# P02_XDS100v2.net
KiCad netlist of a schematic drawn in Altium Designer
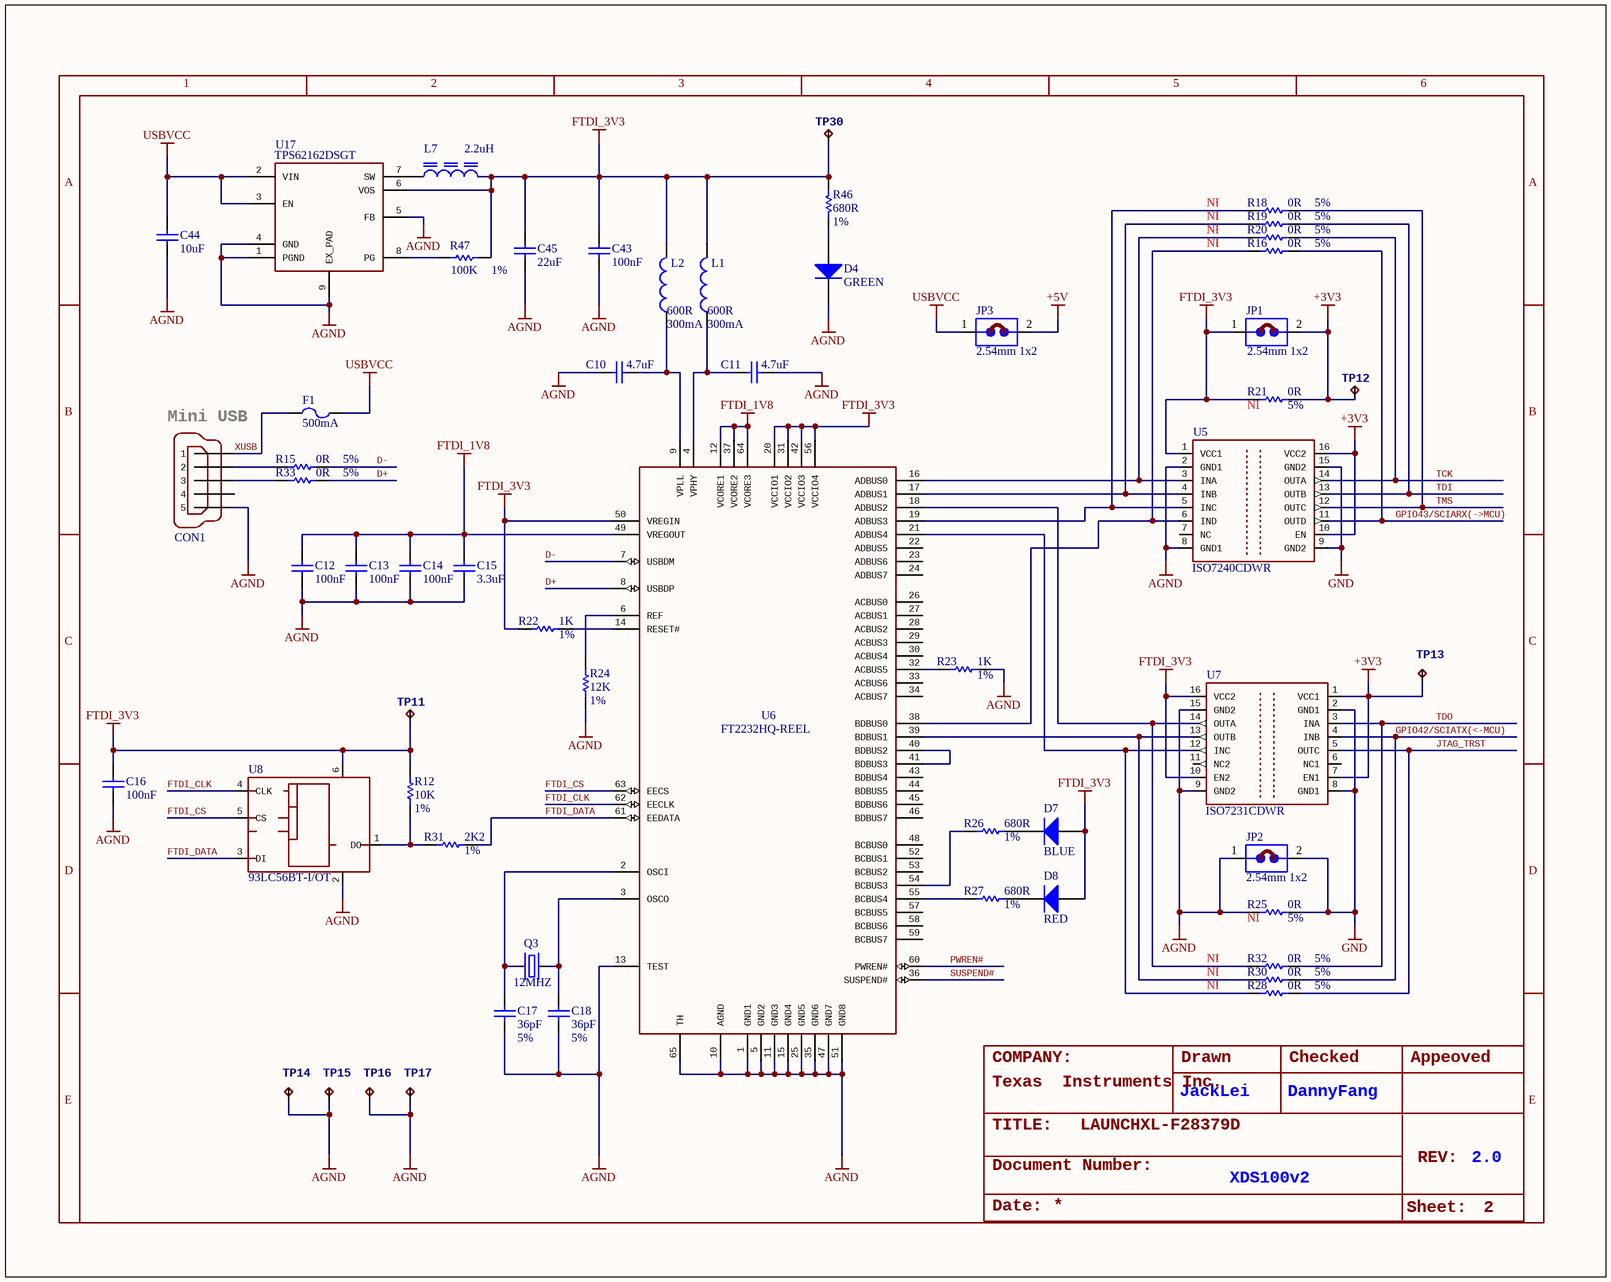
[diagram p0: P02_XDS100v2.SchDoc]

(export (version "E")
  (design (tool "Eeschema 10.0.6"))
  (components
    (comp (ref "C10")
      (value "4.7uF")
      (footprint "C0402")
      (description "CAP,4.7UF,+/-20%,X5R,6.3V,SMD0402 fix PN add D（20151023）")
      (fields
        (field (name "MANUFACTURER") "MURATA")
        (field (name "MANUFACTURER PART NUMBER") "GRM155R60J475ME47D")
      )
      (libsource (lib "Embest") (part "C"))
    )
    (comp (ref "C11")
      (value "4.7uF")
      (footprint "C0402")
      (description "CAP,4.7UF,+/-20%,X5R,6.3V,SMD0402 fix PN add D（20151023）")
      (fields
        (field (name "MANUFACTURER") "MURATA")
        (field (name "MANUFACTURER PART NUMBER") "GRM155R60J475ME47D")
      )
      (libsource (lib "Embest") (part "C"))
    )
    (comp (ref "C12")
      (value "100nF")
      (footprint "C0402")
      (description "CAP,100NF(0.1uf),+/-10%,X5R,10V,SMD0402")
      (fields
        (field (name "MANUFACTURER") "MURATA")
        (field (name "MANUFACTURER PART NUMBER") "GRM155R61A104KA01D")
      )
      (libsource (lib "Embest") (part "C"))
    )
    (comp (ref "C13")
      (value "100nF")
      (footprint "C0402")
      (description "CAP,100NF(0.1uf),+/-10%,X5R,10V,SMD0402")
      (fields
        (field (name "MANUFACTURER") "MURATA")
        (field (name "MANUFACTURER PART NUMBER") "GRM155R61A104KA01D")
      )
      (libsource (lib "Embest") (part "C"))
    )
    (comp (ref "C14")
      (value "100nF")
      (footprint "C0402")
      (description "CAP,100NF(0.1uf),+/-10%,X5R,10V,SMD0402")
      (fields
        (field (name "MANUFACTURER") "MURATA")
        (field (name "MANUFACTURER PART NUMBER") "GRM155R61A104KA01D")
      )
      (libsource (lib "Embest") (part "C"))
    )
    (comp (ref "C15")
      (value "3.3uF")
      (footprint "C0603")
      (description "CAP,3.3uF,+/-10%,X5R,10V,SMD0603")
      (fields
        (field (name "MANUFACTURER") "MURATA")
        (field (name "MANUFACTURER PART NUMBER") "GRM188R61A335KE15D")
      )
      (libsource (lib "Embest") (part "C"))
    )
    (comp (ref "C16")
      (value "100nF")
      (footprint "C0402")
      (description "CAP,100NF(0.1uf),+/-10%,X5R,10V,SMD0402")
      (fields
        (field (name "MANUFACTURER") "MURATA")
        (field (name "MANUFACTURER PART NUMBER") "GRM155R61A104KA01D")
      )
      (libsource (lib "Embest") (part "C"))
    )
    (comp (ref "C17")
      (value "36pF")
      (footprint "C0402")
      (description "CAP,36pF,+/-5%,C0G,50V,SMD0402")
      (fields
        (field (name "RATING") "5%")
        (field (name "MANUFACTURER") "MURATA")
        (field (name "MANUFACTURER PART NUMBER") "GRM1555C1H360JA01D")
      )
      (libsource (lib "Embest") (part "C"))
    )
    (comp (ref "C18")
      (value "36pF")
      (footprint "C0402")
      (description "CAP,36pF,+/-5%,C0G,50V,SMD0402")
      (fields
        (field (name "RATING") "5%")
        (field (name "MANUFACTURER") "MURATA")
        (field (name "MANUFACTURER PART NUMBER") "GRM1555C1H360JA01D")
      )
      (libsource (lib "Embest") (part "C"))
    )
    (comp (ref "C43")
      (value "100nF")
      (footprint "C0402")
      (description "CAP,100NF(0.1uf),+/-10%,X5R,10V,SMD0402")
      (fields
        (field (name "MANUFACTURER") "MURATA")
        (field (name "MANUFACTURER PART NUMBER") "GRM155R61A104KA01D")
      )
      (libsource (lib "Embest") (part "C"))
    )
    (comp (ref "C44")
      (value "10uF")
      (footprint "C1210")
      (description "CAP,10UF,+/-10%,X7R,25V,SMD1210")
      (fields
        (field (name "MANUFACTURER") "MURATA")
        (field (name "MANUFACTURER PART NUMBER") "GRM32DR71E106KA12L")
      )
      (libsource (lib "Embest") (part "C"))
    )
    (comp (ref "C45")
      (value "22uF")
      (footprint "C1210")
      (description "CAP,22UF,+/-10%,X7R,25V,SMD1210")
      (fields
        (field (name "MANUFACTURER") "MURATA")
        (field (name "MANUFACTURER PART NUMBER") "GRM32ER61E226KE15L")
      )
      (libsource (lib "Embest") (part "C"))
    )
    (comp (ref "CON1")
      (value "897-43-005-00-100001")
      (footprint "USB-MINI-B-5P-SMD")
      (description "Connector,MiniUSB B port,5 position,Right Angle,Gold flash 30u,black,SMD")
      (fields (field (name "MANUFACTURER") "MILL-MAX"))
      (libsource (lib "Embest") (part "MINI-USB-32005-201"))
    )
    (comp (ref "D4")
      (value "GREEN")
      (footprint "D0805")
      (description "LED, Bright GREEN , 570nm,30mA,SMD,0805")
      (fields (field (name "MANUFACTURER") "WURTH") (field (name "MANUFACTURER PART NUMBER") "150080VS75000"))
      (libsource (lib "Embest") (part "D"))
    )
    (comp (ref "D7")
      (value "BLUE")
      (footprint "D0805")
      (description "LED, BLUE ,470NM, 30mA,SMD,0805")
      (fields (field (name "MANUFACTURER") "WURTH") (field (name "MANUFACTURER PART NUMBER") "150080BS75000"))
      (libsource (lib "Embest") (part "D"))
    )
    (comp (ref "D8")
      (value "RED")
      (footprint "D0805")
      (description "LED, SUPPER RED ,630NM,30mA, SMD,0805")
      (fields (field (name "MANUFACTURER") "WURTH") (field (name "MANUFACTURER PART NUMBER") "150080SS75000"))
      (libsource (lib "Embest") (part "D"))
    )
    (comp (ref "F1")
      (value "500mA")
      (footprint "FUSM4632X85N")
      (description "PTC RESETTABLE .50A 15V 1812")
      (fields (field (name "MANUFACTURER") "BOURNS") (field (name "MANUFACTURER PART NUMBER") "MF-MSMF050-2"))
      (libsource (lib "Embest") (part "F"))
    )
    (comp (ref "JP1")
      (value "2.54mm 1x2")
      (footprint "HDRV2W64P254_1X2_508X250X850P")
      (fields
        (field (name "MANUFACTURER") "CHIN-BAN")
        (field (name "MANUFACTURER PART NUMBER") "P6E02A-602530-B1")
      )
      (libsource (lib "Embest") (part "SIP2"))
    )
    (comp (ref "JP2")
      (value "2.54mm 1x2")
      (footprint "HDRV2W64P254_1X2_508X250X850P")
      (fields
        (field (name "MANUFACTURER") "CHIN-BAN")
        (field (name "MANUFACTURER PART NUMBER") "P6E02A-602530-B1")
      )
      (libsource (lib "Embest") (part "SIP2"))
    )
    (comp (ref "JP3")
      (value "2.54mm 1x2")
      (footprint "HDRV2W64P254_1X2_508X250X850P")
      (fields
        (field (name "MANUFACTURER") "CHIN-BAN")
        (field (name "MANUFACTURER PART NUMBER") "P6E02A-602530-B1")
      )
      (libsource (lib "Embest") (part "SIP2"))
    )
    (comp (ref "L1")
      (value "600R")
      (footprint "L0402")
      (description "Ferrite Bead,600ohm@100MHz,+/-25%,300mA,0.6ohm,SMD0402")
      (fields
        (field (name "RATING") "300mA")
        (field (name "MANUFACTURER") "MURATA")
        (field (name "MANUFACTURER PART NUMBER") "BLM15AG601SN1D")
      )
      (libsource (lib "Embest") (part "FB"))
    )
    (comp (ref "L2")
      (value "600R")
      (footprint "L0402")
      (description "Ferrite Bead,600ohm@100MHz,+/-25%,300mA,0.6ohm,SMD0402")
      (fields
        (field (name "RATING") "300mA")
        (field (name "MANUFACTURER") "MURATA")
        (field (name "MANUFACTURER PART NUMBER") "BLM15AG601SN1D")
      )
      (libsource (lib "Embest") (part "FB"))
    )
    (comp (ref "L7")
      (value "2.2uH")
      (footprint "INDC300X300X180N")
      (description "Power Inductor,Magnetic shielded,2.2uH,1.6A,0.06ohm,3.0X3.0X1.8mm,SMD")
      (fields
        (field (name "MANUFACTURER") "SUMIDA")
        (field (name "MANUFACTURER PART NUMBER") "CDRH2D18/HPNP-2R2NC")
      )
      (libsource (lib "Embest") (part "L"))
    )
    (comp (ref "Q3")
      (value "12MHZ")
      (footprint "XTAL1140X470X330N")
      (description "Crystal 12MHz ±30ppm (Tol) ±30ppm (Stability) 18pF FUND 50Ohm 2-Pin HC-49/US SMD T/R")
      (fields
        (field (name "MANUFACTURER") "ABRACON")
        (field (name "MANUFACTURER PART NUMBER") "ABLS2-12.000MHZ-D4Y-T")
      )
      (libsource (lib "Embest") (part "X"))
    )
    (comp (ref "R12")
      (value "10K")
      (footprint "R0402")
      (description "RES,10K,+/-1%,1/16W,SMD0402")
      (fields
        (field (name "RATING") "1%")
        (field (name "MANUFACTURER") "YAGEO")
        (field (name "MANUFACTURER PART NUMBER") "RC0402FR-0710KL")
      )
      (libsource (lib "Embest") (part "R"))
    )
    (comp (ref "R15")
      (value "0R")
      (footprint "R0402")
      (description "RES,0R,+/-5%,1/16W,SMD0402")
      (fields
        (field (name "RATING") "5%")
        (field (name "MANUFACTURER") "YAGEO")
        (field (name "MANUFACTURER PART NUMBER") "RC0402JR-070RL")
      )
      (libsource (lib "Embest") (part "R"))
    )
    (comp (ref "R16")
      (value "0R")
      (footprint "R1206")
      (description "RES,0R,+/-5%,1/2W,SMD1206")
      (fields
        (field (name "RATING") "5%")
        (field (name "ASSY") "NI")
        (field (name "MANUFACTURER") "YAGEO")
        (field (name "MANUFACTURER PART NUMBER") "RC1206JR-7W0RL")
      )
      (libsource (lib "Embest") (part "R"))
    )
    (comp (ref "R18")
      (value "0R")
      (footprint "R1206")
      (description "RES,0R,+/-5%,1/2W,SMD1206")
      (fields
        (field (name "RATING") "5%")
        (field (name "ASSY") "NI")
        (field (name "MANUFACTURER") "YAGEO")
        (field (name "MANUFACTURER PART NUMBER") "RC1206JR-7W0RL")
      )
      (libsource (lib "Embest") (part "R"))
    )
    (comp (ref "R19")
      (value "0R")
      (footprint "R1206")
      (description "RES,0R,+/-5%,1/2W,SMD1206")
      (fields
        (field (name "RATING") "5%")
        (field (name "ASSY") "NI")
        (field (name "MANUFACTURER") "YAGEO")
        (field (name "MANUFACTURER PART NUMBER") "RC1206JR-7W0RL")
      )
      (libsource (lib "Embest") (part "R"))
    )
    (comp (ref "R20")
      (value "0R")
      (footprint "R1206")
      (description "RES,0R,+/-5%,1/2W,SMD1206")
      (fields
        (field (name "RATING") "5%")
        (field (name "ASSY") "NI")
        (field (name "MANUFACTURER") "YAGEO")
        (field (name "MANUFACTURER PART NUMBER") "RC1206JR-7W0RL")
      )
      (libsource (lib "Embest") (part "R"))
    )
    (comp (ref "R21")
      (value "0R")
      (footprint "R1206")
      (description "RES,0R,+/-5%,1/2W,SMD1206")
      (fields
        (field (name "RATING") "5%")
        (field (name "ASSY") "NI")
        (field (name "MANUFACTURER") "YAGEO")
        (field (name "MANUFACTURER PART NUMBER") "RC1206JR-7W0RL")
      )
      (libsource (lib "Embest") (part "R"))
    )
    (comp (ref "R22")
      (value "1K")
      (footprint "R0402")
      (description "RES,1K,+/-1%,1/16W,SMD0402")
      (fields
        (field (name "RATING") "1%")
        (field (name "MANUFACTURER") "YAGEO")
        (field (name "MANUFACTURER PART NUMBER") "RC0402FR-071KL")
      )
      (libsource (lib "Embest") (part "R"))
    )
    (comp (ref "R23")
      (value "1K")
      (footprint "R0402")
      (description "RES,1K,+/-1%,1/16W,SMD0402")
      (fields
        (field (name "RATING") "1%")
        (field (name "MANUFACTURER") "YAGEO")
        (field (name "MANUFACTURER PART NUMBER") "RC0402FR-071KL")
      )
      (libsource (lib "Embest") (part "R"))
    )
    (comp (ref "R24")
      (value "12K")
      (footprint "R0402")
      (description "RES,12K,+/-1%,1/16W,SMD0402")
      (fields
        (field (name "RATING") "1%")
        (field (name "MANUFACTURER") "YAGEO")
        (field (name "MANUFACTURER PART NUMBER") "RC0402FR-0712KL")
      )
      (libsource (lib "Embest") (part "R"))
    )
    (comp (ref "R25")
      (value "0R")
      (footprint "R1206")
      (description "RES,0R,+/-5%,1/2W,SMD1206")
      (fields
        (field (name "RATING") "5%")
        (field (name "ASSY") "NI")
        (field (name "MANUFACTURER") "YAGEO")
        (field (name "MANUFACTURER PART NUMBER") "RC1206JR-7W0RL")
      )
      (libsource (lib "Embest") (part "R"))
    )
    (comp (ref "R26")
      (value "680R")
      (footprint "R0402")
      (description "RES,680R,+/-1%,1/16W,SMD0402")
      (fields
        (field (name "RATING") "1%")
        (field (name "MANUFACTURER") "YAGEO")
        (field (name "MANUFACTURER PART NUMBER") "RC0402FR-07680RL")
      )
      (libsource (lib "Embest") (part "R"))
    )
    (comp (ref "R27")
      (value "680R")
      (footprint "R0402")
      (description "RES,680R,+/-1%,1/16W,SMD0402")
      (fields
        (field (name "RATING") "1%")
        (field (name "MANUFACTURER") "YAGEO")
        (field (name "MANUFACTURER PART NUMBER") "RC0402FR-07680RL")
      )
      (libsource (lib "Embest") (part "R"))
    )
    (comp (ref "R28")
      (value "0R")
      (footprint "R1206")
      (description "RES,0R,+/-5%,1/2W,SMD1206")
      (fields
        (field (name "RATING") "5%")
        (field (name "ASSY") "NI")
        (field (name "MANUFACTURER") "YAGEO")
        (field (name "MANUFACTURER PART NUMBER") "RC1206JR-7W0RL")
      )
      (libsource (lib "Embest") (part "R"))
    )
    (comp (ref "R30")
      (value "0R")
      (footprint "R1206")
      (description "RES,0R,+/-5%,1/2W,SMD1206")
      (fields
        (field (name "RATING") "5%")
        (field (name "ASSY") "NI")
        (field (name "MANUFACTURER") "YAGEO")
        (field (name "MANUFACTURER PART NUMBER") "RC1206JR-7W0RL")
      )
      (libsource (lib "Embest") (part "R"))
    )
    (comp (ref "R31")
      (value "2K2")
      (footprint "R0402")
      (description "RES,2K2,+/-1%,1/16W,SMD0402")
      (fields
        (field (name "RATING") "1%")
        (field (name "MANUFACTURER") "YAGEO")
        (field (name "MANUFACTURER PART NUMBER") "RC0402FR-072K2L")
      )
      (libsource (lib "Embest") (part "R"))
    )
    (comp (ref "R32")
      (value "0R")
      (footprint "R1206")
      (description "RES,0R,+/-5%,1/2W,SMD1206")
      (fields
        (field (name "RATING") "5%")
        (field (name "ASSY") "NI")
        (field (name "MANUFACTURER") "YAGEO")
        (field (name "MANUFACTURER PART NUMBER") "RC1206JR-7W0RL")
      )
      (libsource (lib "Embest") (part "R"))
    )
    (comp (ref "R33")
      (value "0R")
      (footprint "R0402")
      (description "RES,0R,+/-5%,1/16W,SMD0402")
      (fields
        (field (name "RATING") "5%")
        (field (name "MANUFACTURER") "YAGEO")
        (field (name "MANUFACTURER PART NUMBER") "RC0402JR-070RL")
      )
      (libsource (lib "Embest") (part "R"))
    )
    (comp (ref "R46")
      (value "680R")
      (footprint "R0402")
      (description "RES,680R,+/-1%,1/16W,SMD0402")
      (fields
        (field (name "RATING") "1%")
        (field (name "MANUFACTURER") "YAGEO")
        (field (name "MANUFACTURER PART NUMBER") "RC0402FR-07680RL")
      )
      (libsource (lib "Embest") (part "R"))
    )
    (comp (ref "R47")
      (value "100K")
      (footprint "R0402")
      (description "RES,100K,+/-1%,1/16W,SMD0402")
      (fields
        (field (name "RATING") "1%")
        (field (name "MANUFACTURER") "YAGEO")
        (field (name "MANUFACTURER PART NUMBER") "RC0402FR-07100KL")
      )
      (libsource (lib "Embest") (part "R"))
    )
    (comp (ref "TP11")
      (value "TESTPAD_TPB1,27")
      (footprint "TESTPAD_B1,27")
      (description "Test pad")
      (libsource (lib "Embest") (part "TESTPAD_TPB1,27"))
    )
    (comp (ref "TP12")
      (value "TESTPAD_TPB1,27")
      (footprint "TESTPAD_B1,27")
      (description "Test pad")
      (libsource (lib "Embest") (part "TESTPAD_TPB1,27"))
    )
    (comp (ref "TP13")
      (value "TESTPAD_TPB1,27")
      (footprint "TESTPAD_B1,27")
      (description "Test pad")
      (libsource (lib "Embest") (part "TESTPAD_TPB1,27"))
    )
    (comp (ref "TP14")
      (value "TESTPAD_TPB1,27")
      (footprint "TESTPAD_B1,27")
      (description "Test pad")
      (libsource (lib "Embest") (part "TESTPAD_TPB1,27"))
    )
    (comp (ref "TP15")
      (value "TESTPAD_TPB1,27")
      (footprint "TESTPAD_B1,27")
      (description "Test pad")
      (libsource (lib "Embest") (part "TESTPAD_TPB1,27"))
    )
    (comp (ref "TP16")
      (value "TESTPAD_TPB1,27")
      (footprint "TESTPAD_B1,27")
      (description "Test pad")
      (libsource (lib "Embest") (part "TESTPAD_TPB1,27"))
    )
    (comp (ref "TP17")
      (value "TESTPAD_TPB1,27")
      (footprint "TESTPAD_B1,27")
      (description "Test pad")
      (libsource (lib "Embest") (part "TESTPAD_TPB1,27"))
    )
    (comp (ref "TP30")
      (value "TESTPAD_TPB1,27")
      (footprint "TESTPAD_B1,27")
      (description "Test pad")
      (libsource (lib "Embest") (part "TESTPAD_TPB1,27"))
    )
    (comp (ref "U$2")
      (value "ROY_JUMPER")
      (footprint "ROY_JUMPER")
      (libsource (lib "Embest") (part "ROY_JUMPER"))
    )
    (comp (ref "U$10")
      (value "ROY_JUMPER")
      (footprint "ROY_JUMPER")
      (libsource (lib "Embest") (part "ROY_JUMPER"))
    )
    (comp (ref "U$11")
      (value "ROY_JUMPER")
      (footprint "ROY_JUMPER")
      (libsource (lib "Embest") (part "ROY_JUMPER"))
    )
    (comp (ref "U5")
      (value "ISO7240CDWR")
      (footprint "SOIC127P1030X265-16N")
      (description "IC DGTL ISO 4CH CMOS 16SOIC,CUSTOMER SUPPLY")
      (fields (field (name "MANUFACTURER") "TI"))
      (libsource (lib "Embest") (part "ISO7240"))
    )
    (comp (ref "U6")
      (value "FT2232HQ-REEL")
      (footprint "QFN50P900X900X100_HS-65N")
      (description "IC,Dual High Speed USB to Multipurpose UART/FIFO IC,FT2232HQ-REEL,QFN-64,SMD")
      (fields (field (name "MANUFACTURER") "FTDI"))
      (libsource (lib "Embest") (part "FT2232HQ"))
    )
    (comp (ref "U7")
      (value "ISO7231CDWR")
      (footprint "SOIC127P1030X265-16N")
      (description "IC DGTL ISO 3CH CMOS 16SOIC,CUSTOMER SUPPLY")
      (fields (field (name "MANUFACTURER") "TI"))
      (libsource (lib "Embest") (part "ISO7231"))
    )
    (comp (ref "U8")
      (value "93LC56BT-I/OT")
      (footprint "SOT23-6")
      (description "IC,EEPROM Serial-Microwire 2K-Bit 128 x 16 2MHz,93LC56BT-I/OT,SOT-23-6,SMD")
      (fields (field (name "MANUFACTURER") "MICROCHIP"))
      (libsource (lib "Embest") (part "93LC56BT"))
    )
    (comp (ref "U17")
      (value "TPS62162DSGT")
      (footprint "WSON50P200X80_HS-9N")
      (description "IC REG BUCK SYNC 3.3V 1A 8WSON")
      (fields (field (name "MANUFACTURER") "TI"))
      (libsource (lib "Embest") (part "TPS62162DSGR"))
    )
  )
  (nets
    (net (code "1") (name "+3V3") (class "Default")
      (node (ref "JP1") (pin "2") (pinfunction "2_2") (pintype "passive"))
      (node (ref "R21") (pin "2") (pinfunction "2_2") (pintype "passive"))
      (node (ref "TP12") (pin "TP") (pinfunction "TP_TP") (pintype "passive"))
      (node (ref "TP13") (pin "TP") (pinfunction "TP_TP") (pintype "passive"))
      (node (ref "U5") (pin "10") (pinfunction "EN_10") (pintype "passive"))
      (node (ref "U5") (pin "16") (pinfunction "VCC2_16") (pintype "power_in"))
      (node (ref "U7") (pin "1") (pinfunction "VCC1_1") (pintype "power_in"))
      (node (ref "U7") (pin "7") (pinfunction "EN1_7") (pintype "passive"))
    )
    (net (code "2") (name "+5V") (class "Default")
      (node (ref "JP3") (pin "2") (pinfunction "2_2") (pintype "passive"))
    )
    (net (code "3") (name "/D+") (class "Default")
      (node (ref "R33") (pin "2") (pinfunction "2_2") (pintype "passive"))
      (node (ref "U6") (pin "8") (pinfunction "USBDP_8") (pintype "bidirectional"))
    )
    (net (code "4") (name "/D-") (class "Default")
      (node (ref "R15") (pin "2") (pinfunction "2_2") (pintype "passive"))
      (node (ref "U6") (pin "7") (pinfunction "USBDM_7") (pintype "bidirectional"))
    )
    (net (code "5") (name "/FTDI_CLK") (class "Default")
      (node (ref "U6") (pin "62") (pinfunction "EECLK_62") (pintype "bidirectional"))
      (node (ref "U8") (pin "4") (pinfunction "CLK_4") (pintype "passive"))
    )
    (net (code "6") (name "/FTDI_CS") (class "Default")
      (node (ref "U6") (pin "63") (pinfunction "EECS_63") (pintype "bidirectional"))
      (node (ref "U8") (pin "5") (pinfunction "CS_5") (pintype "passive"))
    )
    (net (code "7") (name "/FTDI_DATA") (class "Default")
      (node (ref "R31") (pin "2") (pinfunction "2_2") (pintype "passive"))
      (node (ref "U6") (pin "61") (pinfunction "EEDATA_61") (pintype "bidirectional"))
      (node (ref "U8") (pin "3") (pinfunction "DI_3") (pintype "passive"))
    )
    (net (code "8") (name "/GPIO42{slash}SCIATX(<-MCU)") (class "Default")
      (node (ref "R30") (pin "2") (pinfunction "2_2") (pintype "passive"))
      (node (ref "U7") (pin "4") (pinfunction "INB_4") (pintype "passive"))
    )
    (net (code "9") (name "/GPIO43{slash}SCIARX(->MCU)") (class "Default")
      (node (ref "R16") (pin "2") (pinfunction "2_2") (pintype "passive"))
      (node (ref "U5") (pin "11") (pinfunction "OUTD_11") (pintype "output"))
    )
    (net (code "10") (name "/JTAG_TRST") (class "Default")
      (node (ref "R28") (pin "2") (pinfunction "2_2") (pintype "passive"))
      (node (ref "U7") (pin "5") (pinfunction "OUTC_5") (pintype "passive"))
    )
    (net (code "11") (name "/PWREN#") (class "Default")
      (node (ref "U6") (pin "60") (pinfunction "PWREN#_60") (pintype "bidirectional"))
    )
    (net (code "12") (name "/SUSPEND#") (class "Default")
      (node (ref "U6") (pin "36") (pinfunction "SUSPEND#_36") (pintype "bidirectional"))
    )
    (net (code "13") (name "/TCK") (class "Default")
      (node (ref "R20") (pin "2") (pinfunction "2_2") (pintype "passive"))
      (node (ref "U5") (pin "14") (pinfunction "OUTA_14") (pintype "output"))
    )
    (net (code "14") (name "/TDI") (class "Default")
      (node (ref "R19") (pin "2") (pinfunction "2_2") (pintype "passive"))
      (node (ref "U5") (pin "13") (pinfunction "OUTB_13") (pintype "output"))
    )
    (net (code "15") (name "/TDO") (class "Default")
      (node (ref "R32") (pin "2") (pinfunction "2_2") (pintype "passive"))
      (node (ref "U7") (pin "3") (pinfunction "INA_3") (pintype "passive"))
    )
    (net (code "16") (name "/TMS") (class "Default")
      (node (ref "R18") (pin "2") (pinfunction "2_2") (pintype "passive"))
      (node (ref "U5") (pin "12") (pinfunction "OUTC_12") (pintype "output"))
    )
    (net (code "17") (name "/XUSB") (class "Default")
      (node (ref "CON1") (pin "1") (pinfunction "1_1") (pintype "passive"))
      (node (ref "F1") (pin "1") (pinfunction "1_1") (pintype "passive"))
    )
    (net (code "18") (name "AGND") (class "Default")
      (node (ref "C10") (pin "1") (pinfunction "1_1") (pintype "passive"))
      (node (ref "C11") (pin "1") (pinfunction "1_1") (pintype "passive"))
      (node (ref "C12") (pin "1") (pinfunction "1_1") (pintype "passive"))
      (node (ref "C13") (pin "1") (pinfunction "1_1") (pintype "passive"))
      (node (ref "C14") (pin "1") (pinfunction "1_1") (pintype "passive"))
      (node (ref "C15") (pin "1") (pinfunction "1_1") (pintype "passive"))
      (node (ref "C16") (pin "1") (pinfunction "1_1") (pintype "passive"))
      (node (ref "C17") (pin "1") (pinfunction "1_1") (pintype "passive"))
      (node (ref "C18") (pin "1") (pinfunction "1_1") (pintype "passive"))
      (node (ref "C43") (pin "1") (pinfunction "1_1") (pintype "passive"))
      (node (ref "C44") (pin "2") (pinfunction "2_2") (pintype "passive"))
      (node (ref "C45") (pin "1") (pinfunction "1_1") (pintype "passive"))
      (node (ref "CON1") (pin "5") (pinfunction "5_5") (pintype "passive"))
      (node (ref "D4") (pin "1") (pinfunction "1_1") (pintype "passive"))
      (node (ref "JP2") (pin "1") (pinfunction "1_1") (pintype "passive"))
      (node (ref "R23") (pin "2") (pinfunction "2_2") (pintype "passive"))
      (node (ref "R24") (pin "1") (pinfunction "1_1") (pintype "passive"))
      (node (ref "R25") (pin "1") (pinfunction "1_1") (pintype "passive"))
      (node (ref "TP14") (pin "TP") (pinfunction "TP_TP") (pintype "passive"))
      (node (ref "TP15") (pin "TP") (pinfunction "TP_TP") (pintype "passive"))
      (node (ref "TP16") (pin "TP") (pinfunction "TP_TP") (pintype "passive"))
      (node (ref "TP17") (pin "TP") (pinfunction "TP_TP") (pintype "passive"))
      (node (ref "U17") (pin "1") (pinfunction "PGND_1") (pintype "passive"))
      (node (ref "U17") (pin "4") (pinfunction "GND_4") (pintype "passive"))
      (node (ref "U17") (pin "5") (pinfunction "FB_5") (pintype "passive"))
      (node (ref "U17") (pin "9") (pinfunction "EX_PAD_9") (pintype "passive"))
      (node (ref "U5") (pin "2") (pinfunction "GND1_2") (pintype "power_in"))
      (node (ref "U5") (pin "8") (pinfunction "GND1_8") (pintype "power_in"))
      (node (ref "U6") (pin "1") (pinfunction "GND1_1") (pintype "power_in"))
      (node (ref "U6") (pin "10") (pinfunction "AGND_10") (pintype "power_in"))
      (node (ref "U6") (pin "11") (pinfunction "GND3_11") (pintype "power_in"))
      (node (ref "U6") (pin "13") (pinfunction "TEST_13") (pintype "power_in"))
      (node (ref "U6") (pin "15") (pinfunction "GND4_15") (pintype "power_in"))
      (node (ref "U6") (pin "25") (pinfunction "GND5_25") (pintype "power_in"))
      (node (ref "U6") (pin "35") (pinfunction "GND6_35") (pintype "power_in"))
      (node (ref "U6") (pin "47") (pinfunction "GND7_47") (pintype "power_in"))
      (node (ref "U6") (pin "5") (pinfunction "GND2_5") (pintype "power_in"))
      (node (ref "U6") (pin "51") (pinfunction "GND8_51") (pintype "power_in"))
      (node (ref "U6") (pin "65") (pinfunction "TH_65") (pintype "power_in"))
      (node (ref "U7") (pin "15") (pinfunction "GND2_15") (pintype "power_in"))
      (node (ref "U7") (pin "9") (pinfunction "GND2_9") (pintype "power_in"))
      (node (ref "U8") (pin "2") (pinfunction "GND_2") (pintype "power_in"))
    )
    (net (code "19") (name "FTDI_1V8") (class "Default")
      (node (ref "C12") (pin "2") (pinfunction "2_2") (pintype "passive"))
      (node (ref "C13") (pin "2") (pinfunction "2_2") (pintype "passive"))
      (node (ref "C14") (pin "2") (pinfunction "2_2") (pintype "passive"))
      (node (ref "C15") (pin "2") (pinfunction "2_2") (pintype "passive"))
      (node (ref "U6") (pin "12") (pinfunction "VCORE1_12") (pintype "power_in"))
      (node (ref "U6") (pin "37") (pinfunction "VCORE2_37") (pintype "power_in"))
      (node (ref "U6") (pin "49") (pinfunction "VREGOUT_49") (pintype "power_in"))
      (node (ref "U6") (pin "64") (pinfunction "VCORE3_64") (pintype "power_in"))
    )
    (net (code "20") (name "FTDI_3V3") (class "Default")
      (node (ref "C16") (pin "2") (pinfunction "2_2") (pintype "passive"))
      (node (ref "C43") (pin "2") (pinfunction "2_2") (pintype "passive"))
      (node (ref "C45") (pin "2") (pinfunction "2_2") (pintype "passive"))
      (node (ref "D7") (pin "2") (pinfunction "2_2") (pintype "passive"))
      (node (ref "D8") (pin "2") (pinfunction "2_2") (pintype "passive"))
      (node (ref "JP1") (pin "1") (pinfunction "1_1") (pintype "passive"))
      (node (ref "L1") (pin "2") (pinfunction "2_2") (pintype "passive"))
      (node (ref "L2") (pin "2") (pinfunction "2_2") (pintype "passive"))
      (node (ref "L7") (pin "1") (pinfunction "1_1") (pintype "passive"))
      (node (ref "R12") (pin "1") (pinfunction "1_1") (pintype "passive"))
      (node (ref "R21") (pin "1") (pinfunction "1_1") (pintype "passive"))
      (node (ref "R22") (pin "1") (pinfunction "1_1") (pintype "passive"))
      (node (ref "R46") (pin "2") (pinfunction "2_2") (pintype "passive"))
      (node (ref "R47") (pin "1") (pinfunction "1_1") (pintype "passive"))
      (node (ref "TP11") (pin "TP") (pinfunction "TP_TP") (pintype "passive"))
      (node (ref "TP30") (pin "TP") (pinfunction "TP_TP") (pintype "passive"))
      (node (ref "U17") (pin "6") (pinfunction "VOS_6") (pintype "passive"))
      (node (ref "U5") (pin "1") (pinfunction "VCC1_1") (pintype "power_in"))
      (node (ref "U6") (pin "20") (pinfunction "VCCIO1_20") (pintype "power_in"))
      (node (ref "U6") (pin "31") (pinfunction "VCCIO2_31") (pintype "power_in"))
      (node (ref "U6") (pin "42") (pinfunction "VCCIO3_42") (pintype "power_in"))
      (node (ref "U6") (pin "50") (pinfunction "VREGIN_50") (pintype "power_in"))
      (node (ref "U6") (pin "56") (pinfunction "VCCIO4_56") (pintype "power_in"))
      (node (ref "U7") (pin "10") (pinfunction "EN2_10") (pintype "passive"))
      (node (ref "U7") (pin "16") (pinfunction "VCC2_16") (pintype "power_in"))
      (node (ref "U8") (pin "6") (pinfunction "VCC_6") (pintype "power_in"))
    )
    (net (code "21") (name "GND") (class "Default")
      (node (ref "JP2") (pin "2") (pinfunction "2_2") (pintype "passive"))
      (node (ref "R25") (pin "2") (pinfunction "2_2") (pintype "passive"))
      (node (ref "U5") (pin "15") (pinfunction "GND2_15") (pintype "power_in"))
      (node (ref "U5") (pin "9") (pinfunction "GND2_9") (pintype "power_in"))
      (node (ref "U7") (pin "2") (pinfunction "GND1_2") (pintype "power_in"))
      (node (ref "U7") (pin "8") (pinfunction "GND1_8") (pintype "power_in"))
    )
    (net (code "22") (name "Net-(CON1-Pad2)") (class "Default")
      (node (ref "CON1") (pin "2") (pinfunction "2_2") (pintype "passive"))
      (node (ref "R15") (pin "1") (pinfunction "1_1") (pintype "passive"))
    )
    (net (code "23") (name "Net-(CON1-Pad3)") (class "Default")
      (node (ref "CON1") (pin "3") (pinfunction "3_3") (pintype "passive"))
      (node (ref "R33") (pin "1") (pinfunction "1_1") (pintype "passive"))
    )
    (net (code "24") (name "Net-(D4-Pad2)") (class "Default")
      (node (ref "D4") (pin "2") (pinfunction "2_2") (pintype "passive"))
      (node (ref "R46") (pin "1") (pinfunction "1_1") (pintype "passive"))
    )
    (net (code "25") (name "Net-(D7-Pad1)") (class "Default")
      (node (ref "D7") (pin "1") (pinfunction "1_1") (pintype "passive"))
      (node (ref "R26") (pin "2") (pinfunction "2_2") (pintype "passive"))
    )
    (net (code "26") (name "Net-(D8-Pad1)") (class "Default")
      (node (ref "D8") (pin "1") (pinfunction "1_1") (pintype "passive"))
      (node (ref "R27") (pin "2") (pinfunction "2_2") (pintype "passive"))
    )
    (net (code "27") (name "Net-(U5-INA)") (class "Default")
      (node (ref "R20") (pin "1") (pinfunction "1_1") (pintype "passive"))
      (node (ref "U5") (pin "3") (pinfunction "INA_3") (pintype "passive"))
      (node (ref "U6") (pin "16") (pinfunction "ADBUS0_16") (pintype "passive"))
    )
    (net (code "28") (name "Net-(U5-INB)") (class "Default")
      (node (ref "R19") (pin "1") (pinfunction "1_1") (pintype "passive"))
      (node (ref "U5") (pin "4") (pinfunction "INB_4") (pintype "passive"))
      (node (ref "U6") (pin "17") (pinfunction "ADBUS1_17") (pintype "passive"))
    )
    (net (code "29") (name "Net-(U5-INC)") (class "Default")
      (node (ref "R18") (pin "1") (pinfunction "1_1") (pintype "passive"))
      (node (ref "U5") (pin "5") (pinfunction "INC_5") (pintype "passive"))
      (node (ref "U6") (pin "19") (pinfunction "ADBUS3_19") (pintype "passive"))
    )
    (net (code "30") (name "Net-(U5-IND)") (class "Default")
      (node (ref "R16") (pin "1") (pinfunction "1_1") (pintype "passive"))
      (node (ref "U5") (pin "6") (pinfunction "IND_6") (pintype "passive"))
      (node (ref "U6") (pin "38") (pinfunction "BDBUS0_38") (pintype "passive"))
    )
    (net (code "31") (name "Net-(U6-ACBUS5)") (class "Default")
      (node (ref "R23") (pin "1") (pinfunction "1_1") (pintype "passive"))
      (node (ref "U6") (pin "32") (pinfunction "ACBUS5_32") (pintype "passive"))
    )
    (net (code "32") (name "Net-(U6-ADBUS2)") (class "Default")
      (node (ref "R32") (pin "1") (pinfunction "1_1") (pintype "passive"))
      (node (ref "U6") (pin "18") (pinfunction "ADBUS2_18") (pintype "passive"))
      (node (ref "U7") (pin "14") (pinfunction "OUTA_14") (pintype "output"))
    )
    (net (code "33") (name "Net-(U6-ADBUS4)") (class "Default")
      (node (ref "R28") (pin "1") (pinfunction "1_1") (pintype "passive"))
      (node (ref "U6") (pin "21") (pinfunction "ADBUS4_21") (pintype "passive"))
      (node (ref "U7") (pin "12") (pinfunction "INC_12") (pintype "output"))
    )
    (net (code "34") (name "Net-(U6-BCBUS3)") (class "Default")
      (node (ref "R26") (pin "1") (pinfunction "1_1") (pintype "passive"))
      (node (ref "U6") (pin "54") (pinfunction "BCBUS3_54") (pintype "passive"))
    )
    (net (code "35") (name "Net-(U6-BCBUS4)") (class "Default")
      (node (ref "R27") (pin "1") (pinfunction "1_1") (pintype "passive"))
      (node (ref "U6") (pin "55") (pinfunction "BCBUS4_55") (pintype "passive"))
    )
    (net (code "36") (name "Net-(U6-BDBUS1)") (class "Default")
      (node (ref "R30") (pin "1") (pinfunction "1_1") (pintype "passive"))
      (node (ref "U6") (pin "39") (pinfunction "BDBUS1_39") (pintype "passive"))
      (node (ref "U7") (pin "13") (pinfunction "OUTB_13") (pintype "output"))
    )
    (net (code "37") (name "Net-(U6-BDBUS2)") (class "Default")
      (node (ref "U6") (pin "40") (pinfunction "BDBUS2_40") (pintype "passive"))
      (node (ref "U6") (pin "41") (pinfunction "BDBUS3_41") (pintype "passive"))
    )
    (net (code "38") (name "Net-(U6-OSCI)") (class "Default")
      (node (ref "C17") (pin "2") (pinfunction "2_2") (pintype "passive"))
      (node (ref "Q3") (pin "1") (pinfunction "1_1") (pintype "passive"))
      (node (ref "U6") (pin "2") (pinfunction "OSCI_2") (pintype "passive"))
    )
    (net (code "39") (name "Net-(U6-OSCO)") (class "Default")
      (node (ref "C18") (pin "2") (pinfunction "2_2") (pintype "passive"))
      (node (ref "Q3") (pin "2") (pinfunction "2_2") (pintype "passive"))
      (node (ref "U6") (pin "3") (pinfunction "OSCO_3") (pintype "passive"))
    )
    (net (code "40") (name "Net-(U6-REF)") (class "Default")
      (node (ref "R24") (pin "2") (pinfunction "2_2") (pintype "passive"))
      (node (ref "U6") (pin "6") (pinfunction "REF_6") (pintype "passive"))
    )
    (net (code "41") (name "Net-(U6-RESET#)") (class "Default")
      (node (ref "R22") (pin "2") (pinfunction "2_2") (pintype "passive"))
      (node (ref "U6") (pin "14") (pinfunction "RESET#_14") (pintype "passive"))
    )
    (net (code "42") (name "Net-(U6-VPHY)") (class "Default")
      (node (ref "C11") (pin "2") (pinfunction "2_2") (pintype "passive"))
      (node (ref "L1") (pin "1") (pinfunction "1_1") (pintype "passive"))
      (node (ref "U6") (pin "4") (pinfunction "VPHY_4") (pintype "passive"))
    )
    (net (code "43") (name "Net-(U6-VPLL)") (class "Default")
      (node (ref "C10") (pin "2") (pinfunction "2_2") (pintype "passive"))
      (node (ref "L2") (pin "1") (pinfunction "1_1") (pintype "passive"))
      (node (ref "U6") (pin "9") (pinfunction "VPLL_9") (pintype "passive"))
    )
    (net (code "44") (name "Net-(U8-DO)") (class "Default")
      (node (ref "R12") (pin "2") (pinfunction "2_2") (pintype "passive"))
      (node (ref "R31") (pin "1") (pinfunction "1_1") (pintype "passive"))
      (node (ref "U8") (pin "1") (pinfunction "DO_1") (pintype "tri_state"))
    )
    (net (code "45") (name "Net-(U17-PG)") (class "Default")
      (node (ref "R47") (pin "2") (pinfunction "2_2") (pintype "passive"))
      (node (ref "U17") (pin "8") (pinfunction "PG_8") (pintype "passive"))
    )
    (net (code "46") (name "Net-(U17-SW)") (class "Default")
      (node (ref "L7") (pin "2") (pinfunction "2_2") (pintype "passive"))
      (node (ref "U17") (pin "7") (pinfunction "SW_7") (pintype "passive"))
    )
    (net (code "47") (name "USBVCC") (class "Default")
      (node (ref "C44") (pin "1") (pinfunction "1_1") (pintype "passive"))
      (node (ref "F1") (pin "2") (pinfunction "2_2") (pintype "passive"))
      (node (ref "JP3") (pin "1") (pinfunction "1_1") (pintype "passive"))
      (node (ref "U17") (pin "2") (pinfunction "VIN_2") (pintype "passive"))
      (node (ref "U17") (pin "3") (pinfunction "EN_3") (pintype "passive"))
    )
    (net (code "48") (name "unconnected-(CON1-Pad4)") (class "Default")
      (node (ref "CON1") (pin "4") (pinfunction "4_4") (pintype "passive"))
    )
    (net (code "49") (name "unconnected-(U5-NC-Pad7)") (class "Default")
      (node (ref "U5") (pin "7") (pinfunction "NC_7") (pintype "passive"))
    )
    (net (code "50") (name "unconnected-(U6-ACBUS0-Pad26)") (class "Default")
      (node (ref "U6") (pin "26") (pinfunction "ACBUS0_26") (pintype "passive"))
    )
    (net (code "51") (name "unconnected-(U6-ACBUS1-Pad27)") (class "Default")
      (node (ref "U6") (pin "27") (pinfunction "ACBUS1_27") (pintype "passive"))
    )
    (net (code "52") (name "unconnected-(U6-ACBUS2-Pad28)") (class "Default")
      (node (ref "U6") (pin "28") (pinfunction "ACBUS2_28") (pintype "passive"))
    )
    (net (code "53") (name "unconnected-(U6-ACBUS3-Pad29)") (class "Default")
      (node (ref "U6") (pin "29") (pinfunction "ACBUS3_29") (pintype "passive"))
    )
    (net (code "54") (name "unconnected-(U6-ACBUS4-Pad30)") (class "Default")
      (node (ref "U6") (pin "30") (pinfunction "ACBUS4_30") (pintype "passive"))
    )
    (net (code "55") (name "unconnected-(U6-ACBUS6-Pad33)") (class "Default")
      (node (ref "U6") (pin "33") (pinfunction "ACBUS6_33") (pintype "passive"))
    )
    (net (code "56") (name "unconnected-(U6-ACBUS7-Pad34)") (class "Default")
      (node (ref "U6") (pin "34") (pinfunction "ACBUS7_34") (pintype "passive"))
    )
    (net (code "57") (name "unconnected-(U6-ADBUS5-Pad22)") (class "Default")
      (node (ref "U6") (pin "22") (pinfunction "ADBUS5_22") (pintype "passive"))
    )
    (net (code "58") (name "unconnected-(U6-ADBUS6-Pad23)") (class "Default")
      (node (ref "U6") (pin "23") (pinfunction "ADBUS6_23") (pintype "passive"))
    )
    (net (code "59") (name "unconnected-(U6-ADBUS7-Pad24)") (class "Default")
      (node (ref "U6") (pin "24") (pinfunction "ADBUS7_24") (pintype "passive"))
    )
    (net (code "60") (name "unconnected-(U6-BCBUS0-Pad48)") (class "Default")
      (node (ref "U6") (pin "48") (pinfunction "BCBUS0_48") (pintype "passive"))
    )
    (net (code "61") (name "unconnected-(U6-BCBUS1-Pad52)") (class "Default")
      (node (ref "U6") (pin "52") (pinfunction "BCBUS1_52") (pintype "passive"))
    )
    (net (code "62") (name "unconnected-(U6-BCBUS2-Pad53)") (class "Default")
      (node (ref "U6") (pin "53") (pinfunction "BCBUS2_53") (pintype "passive"))
    )
    (net (code "63") (name "unconnected-(U6-BCBUS5-Pad57)") (class "Default")
      (node (ref "U6") (pin "57") (pinfunction "BCBUS5_57") (pintype "passive"))
    )
    (net (code "64") (name "unconnected-(U6-BCBUS6-Pad58)") (class "Default")
      (node (ref "U6") (pin "58") (pinfunction "BCBUS6_58") (pintype "passive"))
    )
    (net (code "65") (name "unconnected-(U6-BCBUS7-Pad59)") (class "Default")
      (node (ref "U6") (pin "59") (pinfunction "BCBUS7_59") (pintype "passive"))
    )
    (net (code "66") (name "unconnected-(U6-BDBUS4-Pad43)") (class "Default")
      (node (ref "U6") (pin "43") (pinfunction "BDBUS4_43") (pintype "passive"))
    )
    (net (code "67") (name "unconnected-(U6-BDBUS5-Pad44)") (class "Default")
      (node (ref "U6") (pin "44") (pinfunction "BDBUS5_44") (pintype "passive"))
    )
    (net (code "68") (name "unconnected-(U6-BDBUS6-Pad45)") (class "Default")
      (node (ref "U6") (pin "45") (pinfunction "BDBUS6_45") (pintype "passive"))
    )
    (net (code "69") (name "unconnected-(U6-BDBUS7-Pad46)") (class "Default")
      (node (ref "U6") (pin "46") (pinfunction "BDBUS7_46") (pintype "passive"))
    )
    (net (code "70") (name "unconnected-(U7-NC1-Pad6)") (class "Default")
      (node (ref "U7") (pin "6") (pinfunction "NC1_6") (pintype "passive"))
    )
    (net (code "71") (name "unconnected-(U7-NC2-Pad11)") (class "Default")
      (node (ref "U7") (pin "11") (pinfunction "NC2_11") (pintype "output"))
    )
  )
)
